# NAND_GATE.net
KiCad netlist of a schematic drawn in Altium Designer
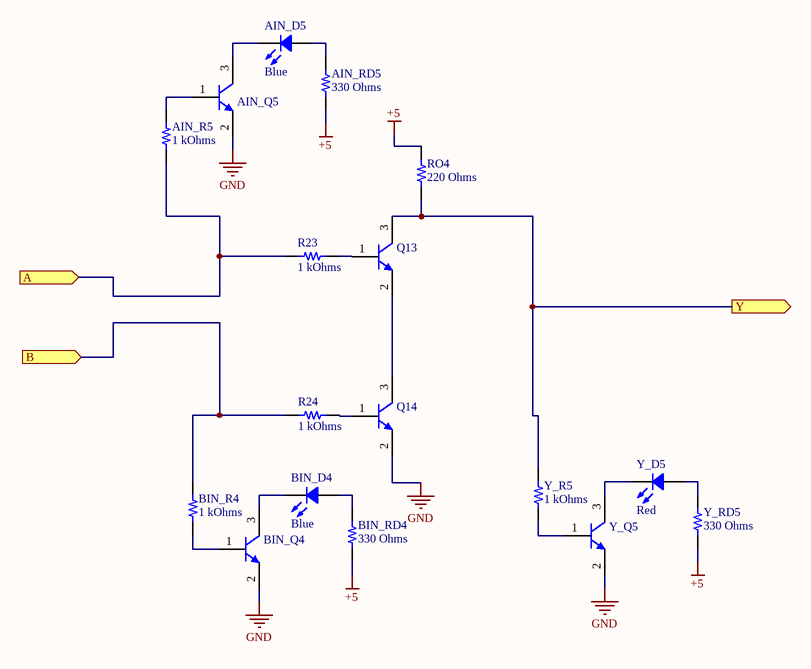
[diagram p0: NAND_GATE.SchDoc]

(export (version "E")
  (design (tool "Eeschema 10.0.6"))
  (components
    (comp (ref "AIN_D5")
      (value "Blue")
      (footprint "LED 0603_1608 BLUE")
      (description "LED BLUE CLEAR 0603 SMD")
      (fields (field (name "PART NUMBER") "IN-S63AT5B") (field (name "MANUFACTURER") "Inolux"))
      (libsource (lib "Celestial Altium Library - altium_library") (part "LED"))
    )
    (comp (ref "AIN_Q5")
      (value "MMSS8050-L-TP")
      (footprint "MCCSEMI SOT-23-3")
      (description "TRANS NPN 25V 1.5A SOT23")
      (fields (field (name "MANUFACTURER") "Micro Commercial Co"))
      (libsource (lib "Celestial Altium Library - altium_library") (part "MCCSEMI NPN SOT-23-3"))
    )
    (comp (ref "AIN_R5")
      (value "1 kOhms")
      (footprint "RES 0603_1608")
      (description "RES SMD 1K OHM 0.1% 1/16W 0603")
      (fields
        (field (name "PART NUMBER") "CPF0603B1K0E")
        (field (name "MANUFACTURER") "TE Connectivity Passive Product")
      )
      (libsource (lib "Celestial Altium Library - altium_library") (part "Resistor"))
    )
    (comp (ref "AIN_RD5")
      (value "330 Ohms")
      (footprint "RES 0603_1608")
      (description "RES 330 OHM 5% 1/10W 0603")
      (fields
        (field (name "PART NUMBER") "RMCF0603JT330R")
        (field (name "MANUFACTURER") "Stackpole Electronics Inc")
      )
      (libsource (lib "Celestial Altium Library - altium_library") (part "Resistor"))
    )
    (comp (ref "BIN_D4")
      (value "Blue")
      (footprint "LED 0603_1608 BLUE")
      (description "LED BLUE CLEAR 0603 SMD")
      (fields (field (name "PART NUMBER") "IN-S63AT5B") (field (name "MANUFACTURER") "Inolux"))
      (libsource (lib "Celestial Altium Library - altium_library") (part "LED"))
    )
    (comp (ref "BIN_Q4")
      (value "MMSS8050-L-TP")
      (footprint "MCCSEMI SOT-23-3")
      (description "TRANS NPN 25V 1.5A SOT23")
      (fields (field (name "MANUFACTURER") "Micro Commercial Co"))
      (libsource (lib "Celestial Altium Library - altium_library") (part "MCCSEMI NPN SOT-23-3"))
    )
    (comp (ref "BIN_R4")
      (value "1 kOhms")
      (footprint "RES 0603_1608")
      (description "RES SMD 1K OHM 0.1% 1/16W 0603")
      (fields
        (field (name "PART NUMBER") "CPF0603B1K0E")
        (field (name "MANUFACTURER") "TE Connectivity Passive Product")
      )
      (libsource (lib "Celestial Altium Library - altium_library") (part "Resistor"))
    )
    (comp (ref "BIN_RD4")
      (value "330 Ohms")
      (footprint "RES 0603_1608")
      (description "RES 330 OHM 5% 1/10W 0603")
      (fields
        (field (name "PART NUMBER") "RMCF0603JT330R")
        (field (name "MANUFACTURER") "Stackpole Electronics Inc")
      )
      (libsource (lib "Celestial Altium Library - altium_library") (part "Resistor"))
    )
    (comp (ref "Q13")
      (value "MMSS8050-L-TP")
      (footprint "MCCSEMI SOT-23-3")
      (description "TRANS NPN 25V 1.5A SOT23")
      (fields (field (name "MANUFACTURER") "Micro Commercial Co"))
      (libsource (lib "Celestial Altium Library - altium_library") (part "MCCSEMI NPN SOT-23-3"))
    )
    (comp (ref "Q14")
      (value "MMSS8050-L-TP")
      (footprint "MCCSEMI SOT-23-3")
      (description "TRANS NPN 25V 1.5A SOT23")
      (fields (field (name "MANUFACTURER") "Micro Commercial Co"))
      (libsource (lib "Celestial Altium Library - altium_library") (part "MCCSEMI NPN SOT-23-3"))
    )
    (comp (ref "R23")
      (value "1 kOhms")
      (footprint "RES 0603_1608")
      (description "RES SMD 1K OHM 0.1% 1/16W 0603")
      (fields
        (field (name "PART NUMBER") "CPF0603B1K0E")
        (field (name "MANUFACTURER") "TE Connectivity Passive Product")
      )
      (libsource (lib "Celestial Altium Library - altium_library") (part "Resistor"))
    )
    (comp (ref "R24")
      (value "1 kOhms")
      (footprint "RES 0603_1608")
      (description "RES SMD 1K OHM 0.1% 1/16W 0603")
      (fields
        (field (name "PART NUMBER") "CPF0603B1K0E")
        (field (name "MANUFACTURER") "TE Connectivity Passive Product")
      )
      (libsource (lib "Celestial Altium Library - altium_library") (part "Resistor"))
    )
    (comp (ref "RO4")
      (value "220 Ohms")
      (footprint "RES 0603_1608")
      (description "RES SMD 220 OHM 0.5% 1/10W 0603")
      (fields
        (field (name "PART NUMBER") "ERA-3AED221V")
        (field (name "MANUFACTURER") "Panasonic Electronic Components")
      )
      (libsource (lib "Celestial Altium Library - altium_library") (part "Resistor"))
    )
    (comp (ref "Y_D5")
      (value "Red")
      (footprint "LED 0603_1608 RED")
      (description "LED RED CLEAR CHIP SMD")
      (fields (field (name "PART NUMBER") "XZMDK53W-8") (field (name "MANUFACTURER") "SunLED"))
      (libsource (lib "Celestial Altium Library - altium_library") (part "LED"))
    )
    (comp (ref "Y_Q5")
      (value "MMSS8050-L-TP")
      (footprint "MCCSEMI SOT-23-3")
      (description "TRANS NPN 25V 1.5A SOT23")
      (fields (field (name "MANUFACTURER") "Micro Commercial Co"))
      (libsource (lib "Celestial Altium Library - altium_library") (part "MCCSEMI NPN SOT-23-3"))
    )
    (comp (ref "Y_R5")
      (value "1 kOhms")
      (footprint "RES 0603_1608")
      (description "RES SMD 1K OHM 0.1% 1/16W 0603")
      (fields
        (field (name "PART NUMBER") "CPF0603B1K0E")
        (field (name "MANUFACTURER") "TE Connectivity Passive Product")
      )
      (libsource (lib "Celestial Altium Library - altium_library") (part "Resistor"))
    )
    (comp (ref "Y_RD5")
      (value "330 Ohms")
      (footprint "RES 0603_1608")
      (description "RES 330 OHM 5% 1/10W 0603")
      (fields
        (field (name "PART NUMBER") "RMCF0603JT330R")
        (field (name "MANUFACTURER") "Stackpole Electronics Inc")
      )
      (libsource (lib "Celestial Altium Library - altium_library") (part "Resistor"))
    )
  )
  (nets
    (net (code "1") (name "+5") (class "Default")
      (node (ref "AIN_RD5") (pin "1") (pinfunction "1_1") (pintype "passive"))
      (node (ref "BIN_RD4") (pin "1") (pinfunction "1_1") (pintype "passive"))
      (node (ref "RO4") (pin "2") (pinfunction "2_2") (pintype "passive"))
      (node (ref "Y_RD5") (pin "1") (pinfunction "1_1") (pintype "passive"))
    )
    (net (code "2") (name "/A") (class "Default")
      (node (ref "AIN_R5") (pin "2") (pinfunction "2_2") (pintype "passive"))
      (node (ref "R23") (pin "1") (pinfunction "1_1") (pintype "passive"))
    )
    (net (code "3") (name "/B") (class "Default")
      (node (ref "BIN_R4") (pin "2") (pinfunction "2_2") (pintype "passive"))
      (node (ref "R24") (pin "1") (pinfunction "1_1") (pintype "passive"))
    )
    (net (code "4") (name "/Y") (class "Default")
      (node (ref "Q13") (pin "3") (pinfunction "C_3") (pintype "passive"))
      (node (ref "RO4") (pin "1") (pinfunction "1_1") (pintype "passive"))
      (node (ref "Y_R5") (pin "2") (pinfunction "2_2") (pintype "passive"))
    )
    (net (code "5") (name "GND") (class "Default")
      (node (ref "AIN_Q5") (pin "2") (pinfunction "E_2") (pintype "passive"))
      (node (ref "BIN_Q4") (pin "2") (pinfunction "E_2") (pintype "passive"))
      (node (ref "Q14") (pin "2") (pinfunction "E_2") (pintype "passive"))
      (node (ref "Y_Q5") (pin "2") (pinfunction "E_2") (pintype "passive"))
    )
    (net (code "6") (name "Net-(AIN_D5-Pad1)") (class "Default")
      (node (ref "AIN_D5") (pin "1") (pinfunction "1_1") (pintype "passive"))
      (node (ref "AIN_RD5") (pin "2") (pinfunction "2_2") (pintype "passive"))
    )
    (net (code "7") (name "Net-(AIN_Q5-B)") (class "Default")
      (node (ref "AIN_Q5") (pin "1") (pinfunction "B_1") (pintype "passive"))
      (node (ref "AIN_R5") (pin "1") (pinfunction "1_1") (pintype "passive"))
    )
    (net (code "8") (name "Net-(AIN_Q5-C)") (class "Default")
      (node (ref "AIN_D5") (pin "2") (pinfunction "2_2") (pintype "passive"))
      (node (ref "AIN_Q5") (pin "3") (pinfunction "C_3") (pintype "passive"))
    )
    (net (code "9") (name "Net-(BIN_D4-Pad1)") (class "Default")
      (node (ref "BIN_D4") (pin "1") (pinfunction "1_1") (pintype "passive"))
      (node (ref "BIN_RD4") (pin "2") (pinfunction "2_2") (pintype "passive"))
    )
    (net (code "10") (name "Net-(BIN_Q4-B)") (class "Default")
      (node (ref "BIN_Q4") (pin "1") (pinfunction "B_1") (pintype "passive"))
      (node (ref "BIN_R4") (pin "1") (pinfunction "1_1") (pintype "passive"))
    )
    (net (code "11") (name "Net-(BIN_Q4-C)") (class "Default")
      (node (ref "BIN_D4") (pin "2") (pinfunction "2_2") (pintype "passive"))
      (node (ref "BIN_Q4") (pin "3") (pinfunction "C_3") (pintype "passive"))
    )
    (net (code "12") (name "Net-(Q13-B)") (class "Default")
      (node (ref "Q13") (pin "1") (pinfunction "B_1") (pintype "passive"))
      (node (ref "R23") (pin "2") (pinfunction "2_2") (pintype "passive"))
    )
    (net (code "13") (name "Net-(Q13-E)") (class "Default")
      (node (ref "Q13") (pin "2") (pinfunction "E_2") (pintype "passive"))
      (node (ref "Q14") (pin "3") (pinfunction "C_3") (pintype "passive"))
    )
    (net (code "14") (name "Net-(Q14-B)") (class "Default")
      (node (ref "Q14") (pin "1") (pinfunction "B_1") (pintype "passive"))
      (node (ref "R24") (pin "2") (pinfunction "2_2") (pintype "passive"))
    )
    (net (code "15") (name "Net-(Y_D5-Pad1)") (class "Default")
      (node (ref "Y_D5") (pin "1") (pinfunction "1_1") (pintype "passive"))
      (node (ref "Y_RD5") (pin "2") (pinfunction "2_2") (pintype "passive"))
    )
    (net (code "16") (name "Net-(Y_Q5-B)") (class "Default")
      (node (ref "Y_Q5") (pin "1") (pinfunction "B_1") (pintype "passive"))
      (node (ref "Y_R5") (pin "1") (pinfunction "1_1") (pintype "passive"))
    )
    (net (code "17") (name "Net-(Y_Q5-C)") (class "Default")
      (node (ref "Y_D5") (pin "2") (pinfunction "2_2") (pintype "passive"))
      (node (ref "Y_Q5") (pin "3") (pinfunction "C_3") (pintype "passive"))
    )
  )
)
